# Kajtu_-DSP_digital_out.net
KiCad netlist of a schematic drawn in Altium Designer
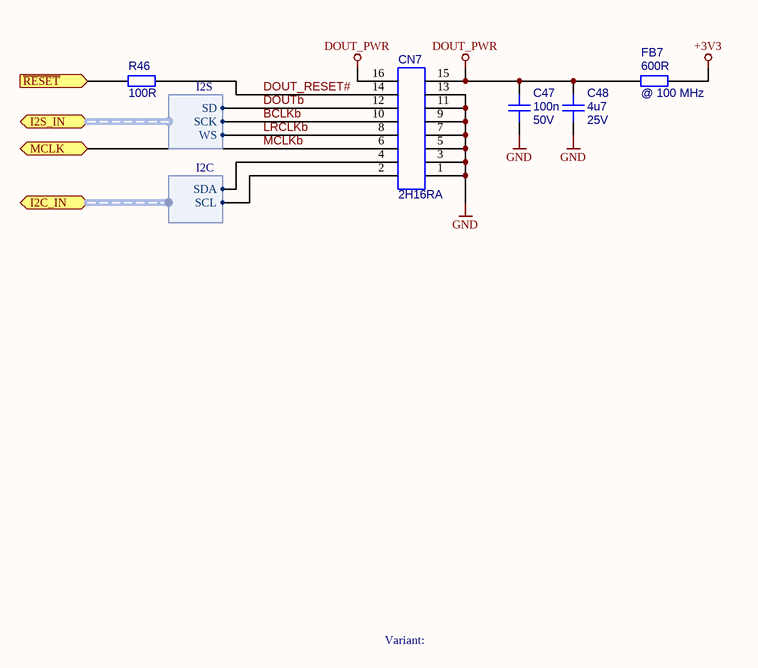
[diagram p0: Kajtuś-DSP_digital_out.SchDoc]

(export (version "E")
  (design (tool "Eeschema 10.0.6"))
  (components
    (comp (ref "C47")
      (value "100n")
      (footprint "C_0603_MA")
      (description "Kondensator ceramiczny SMD")
      (fields (field (name "PART NUMBER") "C_0603_100n_50V_X7R") (field (name "VOLTAGE") "50V"))
      (libsource (lib "AD_ostry_intlib") (part "C_0603_100n_50V_X7R"))
    )
    (comp (ref "C48")
      (value "4u7")
      (footprint "C_1206_MA")
      (description "Kondensator ceramiczny SMD")
      (fields
        (field (name "PART NUMBER") "C_1206_4u7_25V_X7R")
        (field (name "MANUFACTURER") "AVX, KEMET")
        (field (name "VOLTAGE") "25V")
      )
      (libsource (lib "AD_ostry_intlib") (part "C_1206_4u7_25V_X7R"))
    )
    (comp (ref "CN7")
      (value "2H16RA")
      (footprint "CN_2H16RA_WE_WR-PHD_61301621021")
      (description "Listwa kołkowa")
      (fields (field (name "PART NUMBER") "CN_2H16RA") (field (name "MANUFACTURER") "Ninigi"))
      (libsource (lib "AD_ostry_intlib") (part "CN_2H16RA"))
    )
    (comp (ref "FB7")
      (value "600R")
      (footprint "R_0603_MA")
      (description "Koralik ferrytowy")
      (fields
        (field (name "MANUFACTURER") "Yageo")
        (field (name "PART NUMBER") "FB_0603_PBY160808T-601Y_600R_1A")
        (field (name "@ FREQUENCY") "@ 100 MHz")
      )
      (libsource (lib "AD_ostry_intlib") (part "FB_0603_PBY160808T-601Y_600R_1A"))
    )
    (comp (ref "R46")
      (value "100R")
      (footprint "R_0603_MA")
      (description "Rezystor SMD")
      (fields (field (name "PART NUMBER") "R_0603_100R_5%") (field (name "MANUFACTURER") "Royal Ohm"))
      (libsource (lib "AD_ostry_intlib") (part "R_0603_100R_5%"))
    )
  )
  (nets
    (net (code "3") (name "+3V3") (class "Default")
      (node (ref "FB7") (pin "2") (pinfunction "2_2") (pintype "passive"))
    )
    (net (code "4") (name "/BCLKb") (class "Default")
      (node (ref "CN7") (pin "10") (pinfunction "10_10") (pintype "passive"))
    )
    (net (code "5") (name "/DOUT_RESET#") (class "Default")
      (node (ref "CN7") (pin "14") (pinfunction "14_14") (pintype "passive"))
      (node (ref "R46") (pin "2") (pinfunction "2_2") (pintype "passive"))
    )
    (net (code "6") (name "/DOUTb") (class "Default")
      (node (ref "CN7") (pin "12") (pinfunction "12_12") (pintype "passive"))
    )
    (net (code "7") (name "/LRCLKb") (class "Default")
      (node (ref "CN7") (pin "8") (pinfunction "8_8") (pintype "passive"))
    )
    (net (code "8") (name "/MCLKb") (class "Default")
      (node (ref "CN7") (pin "6") (pinfunction "6_6") (pintype "passive"))
    )
    (net (code "9") (name "/SCL") (class "Default")
      (node (ref "CN7") (pin "2") (pinfunction "2_2") (pintype "passive"))
    )
    (net (code "10") (name "/SDA") (class "Default")
      (node (ref "CN7") (pin "4") (pinfunction "4_4") (pintype "passive"))
    )
    (net (code "13") (name "/~{RESET}") (class "Default")
      (node (ref "R46") (pin "1") (pinfunction "1_1") (pintype "passive"))
    )
    (net (code "14") (name "DOUT_PWR") (class "Default")
      (node (ref "C47") (pin "1") (pinfunction "1_1") (pintype "passive"))
      (node (ref "C48") (pin "1") (pinfunction "1_1") (pintype "passive"))
      (node (ref "CN7") (pin "15") (pinfunction "15_15") (pintype "passive"))
      (node (ref "CN7") (pin "16") (pinfunction "16_16") (pintype "passive"))
      (node (ref "FB7") (pin "1") (pinfunction "1_1") (pintype "passive"))
    )
    (net (code "15") (name "GND") (class "Default")
      (node (ref "C47") (pin "2") (pinfunction "2_2") (pintype "passive"))
      (node (ref "C48") (pin "2") (pinfunction "2_2") (pintype "passive"))
      (node (ref "CN7") (pin "1") (pinfunction "1_1") (pintype "passive"))
      (node (ref "CN7") (pin "11") (pinfunction "11_11") (pintype "passive"))
      (node (ref "CN7") (pin "13") (pinfunction "13_13") (pintype "passive"))
      (node (ref "CN7") (pin "3") (pinfunction "3_3") (pintype "passive"))
      (node (ref "CN7") (pin "5") (pinfunction "5_5") (pintype "passive"))
      (node (ref "CN7") (pin "7") (pinfunction "7_7") (pintype "passive"))
      (node (ref "CN7") (pin "9") (pinfunction "9_9") (pintype "passive"))
    )
  )
)
